# Sheet_1_2022-06-28.net
KiCad netlist of a schematic drawn in Altium Designer
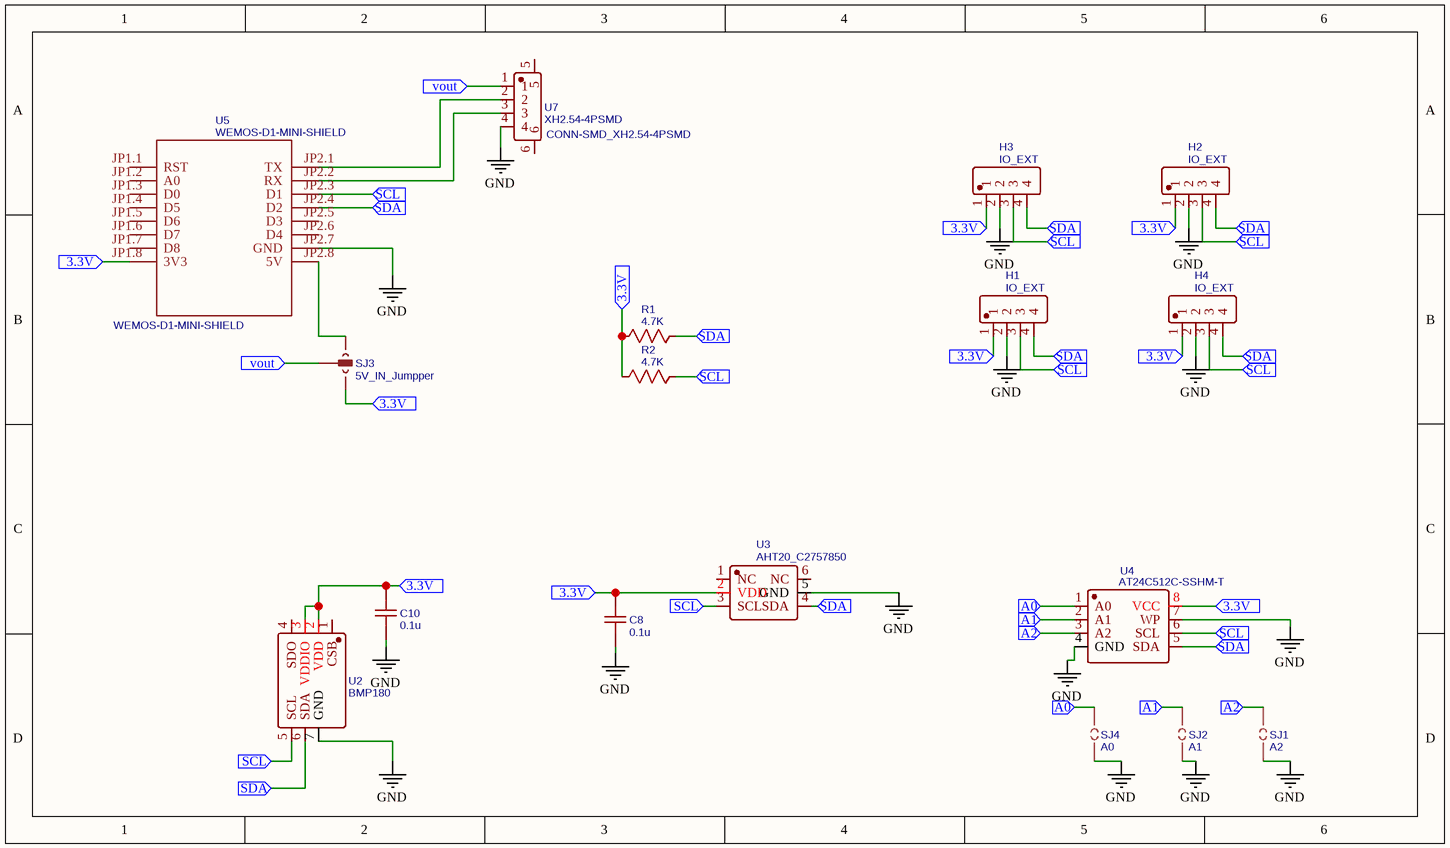
[diagram p0: Sheet_1_2022-06-28.schdoc]

(export (version "E")
  (design (tool "Eeschema 10.0.6"))
  (components
    (comp (ref "C8")
      (value "0.1u")
      (fields (field (name "CONTRIBUTOR") "LCEDA_Lib"))
      (libsource (lib "altium-import") (part "root_1_0.1u_"))
    )
    (comp (ref "C10")
      (value "0.1u")
      (fields (field (name "CONTRIBUTOR") "LCEDA_Lib"))
      (libsource (lib "altium-import") (part "root_1_0.1u_"))
    )
    (comp (ref "H1")
      (value "IO_EXT")
      (fields
        (field (name "BOM_SUPPLIER PART") "C706876")
        (field (name "BOM_MANUFACTURER PART") "X6511WV-04H-C30D60")
        (field (name "CONTRIBUTOR") "LCSC")
      )
      (libsource (lib "altium-import") (part "root_1_IO_EXT_"))
    )
    (comp (ref "H2")
      (value "IO_EXT")
      (fields
        (field (name "BOM_SUPPLIER PART") "C706876")
        (field (name "BOM_MANUFACTURER PART") "X6511WV-04H-C30D60")
        (field (name "CONTRIBUTOR") "LCSC")
      )
      (libsource (lib "altium-import") (part "root_1_IO_EXT_"))
    )
    (comp (ref "H3")
      (value "IO_EXT")
      (fields
        (field (name "BOM_SUPPLIER PART") "C706876")
        (field (name "BOM_MANUFACTURER PART") "X6511WV-04H-C30D60")
        (field (name "CONTRIBUTOR") "LCSC")
      )
      (libsource (lib "altium-import") (part "root_1_IO_EXT_"))
    )
    (comp (ref "H4")
      (value "IO_EXT")
      (fields
        (field (name "BOM_SUPPLIER PART") "C706876")
        (field (name "BOM_MANUFACTURER PART") "X6511WV-04H-C30D60")
        (field (name "CONTRIBUTOR") "LCSC")
      )
      (libsource (lib "altium-import") (part "root_1_IO_EXT_"))
    )
    (comp (ref "R1")
      (value "4.7K")
      (fields (field (name "CONTRIBUTOR") "LCEDA_Lib"))
      (libsource (lib "altium-import") (part "root_2_4.7K_"))
    )
    (comp (ref "R2")
      (value "4.7K")
      (fields (field (name "CONTRIBUTOR") "LCEDA_Lib"))
      (libsource (lib "altium-import") (part "root_2_4.7K_"))
    )
    (comp (ref "SJ1")
      (value "A2")
      (fields (field (name "CONTRIBUTOR") "torusww"))
      (libsource (lib "altium-import") (part "root_1_A2_"))
    )
    (comp (ref "SJ2")
      (value "A1")
      (fields (field (name "CONTRIBUTOR") "torusww"))
      (libsource (lib "altium-import") (part "root_1_A1_"))
    )
    (comp (ref "SJ3")
      (value "5V_IN_Jumpper")
      (fields (field (name "CONTRIBUTOR") "SparkFun"))
      (libsource (lib "altium-import") (part "root_0_5V_IN_Jumpper_"))
    )
    (comp (ref "SJ4")
      (value "A0")
      (fields (field (name "CONTRIBUTOR") "torusww"))
      (libsource (lib "altium-import") (part "root_1_A0_"))
    )
    (comp (ref "U2")
      (value "BMP180")
      (fields (field (name "BOM_SUPPLIER PART") "C438474") (field (name "CONTRIBUTOR") "LCSC"))
      (libsource (lib "altium-import") (part "root_3_BMP180_"))
    )
    (comp (ref "U3")
      (value "AHT20_C2757850")
      (fields
        (field (name "BOM_SUPPLIER PART") "C2757850")
        (field (name "BOM_MANUFACTURER PART") "AHT20")
        (field (name "CONTRIBUTOR") "LCSC")
      )
      (libsource (lib "altium-import") (part "root_0_AHT20_C2757850_"))
    )
    (comp (ref "U4")
      (value "AT24C512C-SSHM-T")
      (fields (field (name "BOM_SUPPLIER PART") "C54668"))
      (libsource (lib "altium-import") (part "root_0_AT24C512C-SSHM-T_"))
    )
    (comp (ref "U5")
      (value "WEMOS-D1-MINI-SHIELD")
      (description "Template for WEMOS D1 mini compatible shields")
      (libsource (lib "altium-import") (part "root_0_WEMOS-D1-MINI-SHIELD_"))
    )
    (comp (ref "U7")
      (value "XH2.54-4PSMD")
      (fields (field (name "BOM_SUPPLIER PART") "C9900001014") (field (name "CONTRIBUTOR") "LCSC"))
      (libsource (lib "altium-import") (part "root_0_XH2.54-4PSMD_"))
    )
  )
  (nets
    (net (code "1") (name "/3.3V") (class "Default")
      (node (ref "C10") (pin "2") (pinfunction "2_2") (pintype "passive"))
      (node (ref "C8") (pin "2") (pinfunction "2_2") (pintype "passive"))
      (node (ref "H1") (pin "1") (pinfunction "1_1") (pintype "passive"))
      (node (ref "H2") (pin "1") (pinfunction "1_1") (pintype "passive"))
      (node (ref "H3") (pin "1") (pinfunction "1_1") (pintype "passive"))
      (node (ref "H4") (pin "1") (pinfunction "1_1") (pintype "passive"))
      (node (ref "R1") (pin "2") (pinfunction "2_2") (pintype "passive"))
      (node (ref "R2") (pin "2") (pinfunction "2_2") (pintype "passive"))
      (node (ref "SJ3") (pin "3") (pinfunction "3_3") (pintype "passive"))
      (node (ref "U2") (pin "2") (pinfunction "VDD_2") (pintype "passive"))
      (node (ref "U2") (pin "3") (pinfunction "VDDIO_3") (pintype "passive"))
      (node (ref "U3") (pin "2") (pinfunction "VDD_2") (pintype "passive"))
      (node (ref "U4") (pin "8") (pinfunction "VCC_8") (pintype "passive"))
      (node (ref "U5") (pin "JP1.8") (pinfunction "3V3_JP1.8") (pintype "passive"))
    )
    (net (code "2") (name "/A0") (class "Default")
      (node (ref "SJ4") (pin "2") (pinfunction "2_2") (pintype "passive"))
      (node (ref "U4") (pin "1") (pinfunction "A0_1") (pintype "passive"))
    )
    (net (code "3") (name "/A1") (class "Default")
      (node (ref "SJ2") (pin "2") (pinfunction "2_2") (pintype "passive"))
      (node (ref "U4") (pin "2") (pinfunction "A1_2") (pintype "passive"))
    )
    (net (code "4") (name "/A2") (class "Default")
      (node (ref "SJ1") (pin "2") (pinfunction "2_2") (pintype "passive"))
      (node (ref "U4") (pin "3") (pinfunction "A2_3") (pintype "passive"))
    )
    (net (code "5") (name "/SCL") (class "Default")
      (node (ref "H1") (pin "3") (pinfunction "3_3") (pintype "passive"))
      (node (ref "H2") (pin "3") (pinfunction "3_3") (pintype "passive"))
      (node (ref "H3") (pin "3") (pinfunction "3_3") (pintype "passive"))
      (node (ref "H4") (pin "3") (pinfunction "3_3") (pintype "passive"))
      (node (ref "R2") (pin "1") (pinfunction "1_1") (pintype "passive"))
      (node (ref "U2") (pin "5") (pinfunction "SCL_5") (pintype "passive"))
      (node (ref "U3") (pin "3") (pinfunction "SCL_3") (pintype "passive"))
      (node (ref "U4") (pin "6") (pinfunction "SCL_6") (pintype "passive"))
      (node (ref "U5") (pin "JP2.3") (pinfunction "D1_JP2.3") (pintype "passive"))
    )
    (net (code "6") (name "/SDA") (class "Default")
      (node (ref "H1") (pin "4") (pinfunction "4_4") (pintype "passive"))
      (node (ref "H2") (pin "4") (pinfunction "4_4") (pintype "passive"))
      (node (ref "H3") (pin "4") (pinfunction "4_4") (pintype "passive"))
      (node (ref "H4") (pin "4") (pinfunction "4_4") (pintype "passive"))
      (node (ref "R1") (pin "1") (pinfunction "1_1") (pintype "passive"))
      (node (ref "U2") (pin "6") (pinfunction "SDA_6") (pintype "passive"))
      (node (ref "U3") (pin "4") (pinfunction "SDA_4") (pintype "passive"))
      (node (ref "U4") (pin "5") (pinfunction "SDA_5") (pintype "passive"))
      (node (ref "U5") (pin "JP2.4") (pinfunction "D2_JP2.4") (pintype "passive"))
    )
    (net (code "7") (name "/vout") (class "Default")
      (node (ref "SJ3") (pin "2") (pinfunction "2_2") (pintype "passive"))
      (node (ref "U7") (pin "1") (pinfunction "1_1") (pintype "passive"))
    )
    (net (code "8") (name "GND") (class "Default")
      (node (ref "C10") (pin "1") (pinfunction "1_1") (pintype "passive"))
      (node (ref "C8") (pin "1") (pinfunction "1_1") (pintype "passive"))
      (node (ref "H1") (pin "2") (pinfunction "2_2") (pintype "passive"))
      (node (ref "H2") (pin "2") (pinfunction "2_2") (pintype "passive"))
      (node (ref "H3") (pin "2") (pinfunction "2_2") (pintype "passive"))
      (node (ref "H4") (pin "2") (pinfunction "2_2") (pintype "passive"))
      (node (ref "SJ1") (pin "1") (pinfunction "1_1") (pintype "passive"))
      (node (ref "SJ2") (pin "1") (pinfunction "1_1") (pintype "passive"))
      (node (ref "SJ4") (pin "1") (pinfunction "1_1") (pintype "passive"))
      (node (ref "U2") (pin "7") (pinfunction "GND_7") (pintype "passive"))
      (node (ref "U3") (pin "5") (pinfunction "GND_5") (pintype "passive"))
      (node (ref "U4") (pin "4") (pinfunction "GND_4") (pintype "passive"))
      (node (ref "U4") (pin "7") (pinfunction "WP_7") (pintype "passive"))
      (node (ref "U5") (pin "JP2.7") (pinfunction "GND_JP2.7") (pintype "passive"))
      (node (ref "U7") (pin "4") (pinfunction "4_4") (pintype "passive"))
    )
    (net (code "9") (name "Net-(U5-5V)") (class "Default")
      (node (ref "SJ3") (pin "1") (pinfunction "1_1") (pintype "passive"))
      (node (ref "U5") (pin "JP2.8") (pinfunction "5V_JP2.8") (pintype "passive"))
    )
    (net (code "10") (name "Net-(U5-RX)") (class "Default")
      (node (ref "U5") (pin "JP2.2") (pinfunction "RX_JP2.2") (pintype "passive"))
      (node (ref "U7") (pin "3") (pinfunction "3_3") (pintype "passive"))
    )
    (net (code "11") (name "Net-(U5-TX)") (class "Default")
      (node (ref "U5") (pin "JP2.1") (pinfunction "TX_JP2.1") (pintype "passive"))
      (node (ref "U7") (pin "2") (pinfunction "2_2") (pintype "passive"))
    )
    (net (code "12") (name "unconnected-(U2-CSB-Pad1)") (class "Default")
      (node (ref "U2") (pin "1") (pinfunction "CSB_1") (pintype "passive"))
    )
    (net (code "13") (name "unconnected-(U2-SDO-Pad4)") (class "Default")
      (node (ref "U2") (pin "4") (pinfunction "SDO_4") (pintype "passive"))
    )
    (net (code "14") (name "unconnected-(U3-NC-Pad1)") (class "Default")
      (node (ref "U3") (pin "1") (pinfunction "NC_1") (pintype "passive"))
    )
    (net (code "15") (name "unconnected-(U3-NC-Pad6)") (class "Default")
      (node (ref "U3") (pin "6") (pinfunction "NC_6") (pintype "passive"))
    )
    (net (code "16") (name "unconnected-(U5-A0-PadJP1.2)") (class "Default")
      (node (ref "U5") (pin "JP1.2") (pinfunction "A0_JP1.2") (pintype "passive"))
    )
    (net (code "17") (name "unconnected-(U5-D0-PadJP1.3)") (class "Default")
      (node (ref "U5") (pin "JP1.3") (pinfunction "D0_JP1.3") (pintype "passive"))
    )
    (net (code "18") (name "unconnected-(U5-D3-PadJP2.5)") (class "Default")
      (node (ref "U5") (pin "JP2.5") (pinfunction "D3_JP2.5") (pintype "passive"))
    )
    (net (code "19") (name "unconnected-(U5-D4-PadJP2.6)") (class "Default")
      (node (ref "U5") (pin "JP2.6") (pinfunction "D4_JP2.6") (pintype "passive"))
    )
    (net (code "20") (name "unconnected-(U5-D5-PadJP1.4)") (class "Default")
      (node (ref "U5") (pin "JP1.4") (pinfunction "D5_JP1.4") (pintype "passive"))
    )
    (net (code "21") (name "unconnected-(U5-D6-PadJP1.5)") (class "Default")
      (node (ref "U5") (pin "JP1.5") (pinfunction "D6_JP1.5") (pintype "passive"))
    )
    (net (code "22") (name "unconnected-(U5-D7-PadJP1.6)") (class "Default")
      (node (ref "U5") (pin "JP1.6") (pinfunction "D7_JP1.6") (pintype "passive"))
    )
    (net (code "23") (name "unconnected-(U5-D8-PadJP1.7)") (class "Default")
      (node (ref "U5") (pin "JP1.7") (pinfunction "D8_JP1.7") (pintype "passive"))
    )
    (net (code "24") (name "unconnected-(U5-RST-PadJP1.1)") (class "Default")
      (node (ref "U5") (pin "JP1.1") (pinfunction "RST_JP1.1") (pintype "passive"))
    )
    (net (code "25") (name "unconnected-(U7-Pad5)") (class "Default")
      (node (ref "U7") (pin "5") (pinfunction "5_5") (pintype "passive"))
    )
    (net (code "26") (name "unconnected-(U7-Pad6)") (class "Default")
      (node (ref "U7") (pin "6") (pinfunction "6_6") (pintype "passive"))
    )
  )
)
